# SEC_3002_HL_Loop1.net
KiCad netlist of a schematic drawn in Altium Designer
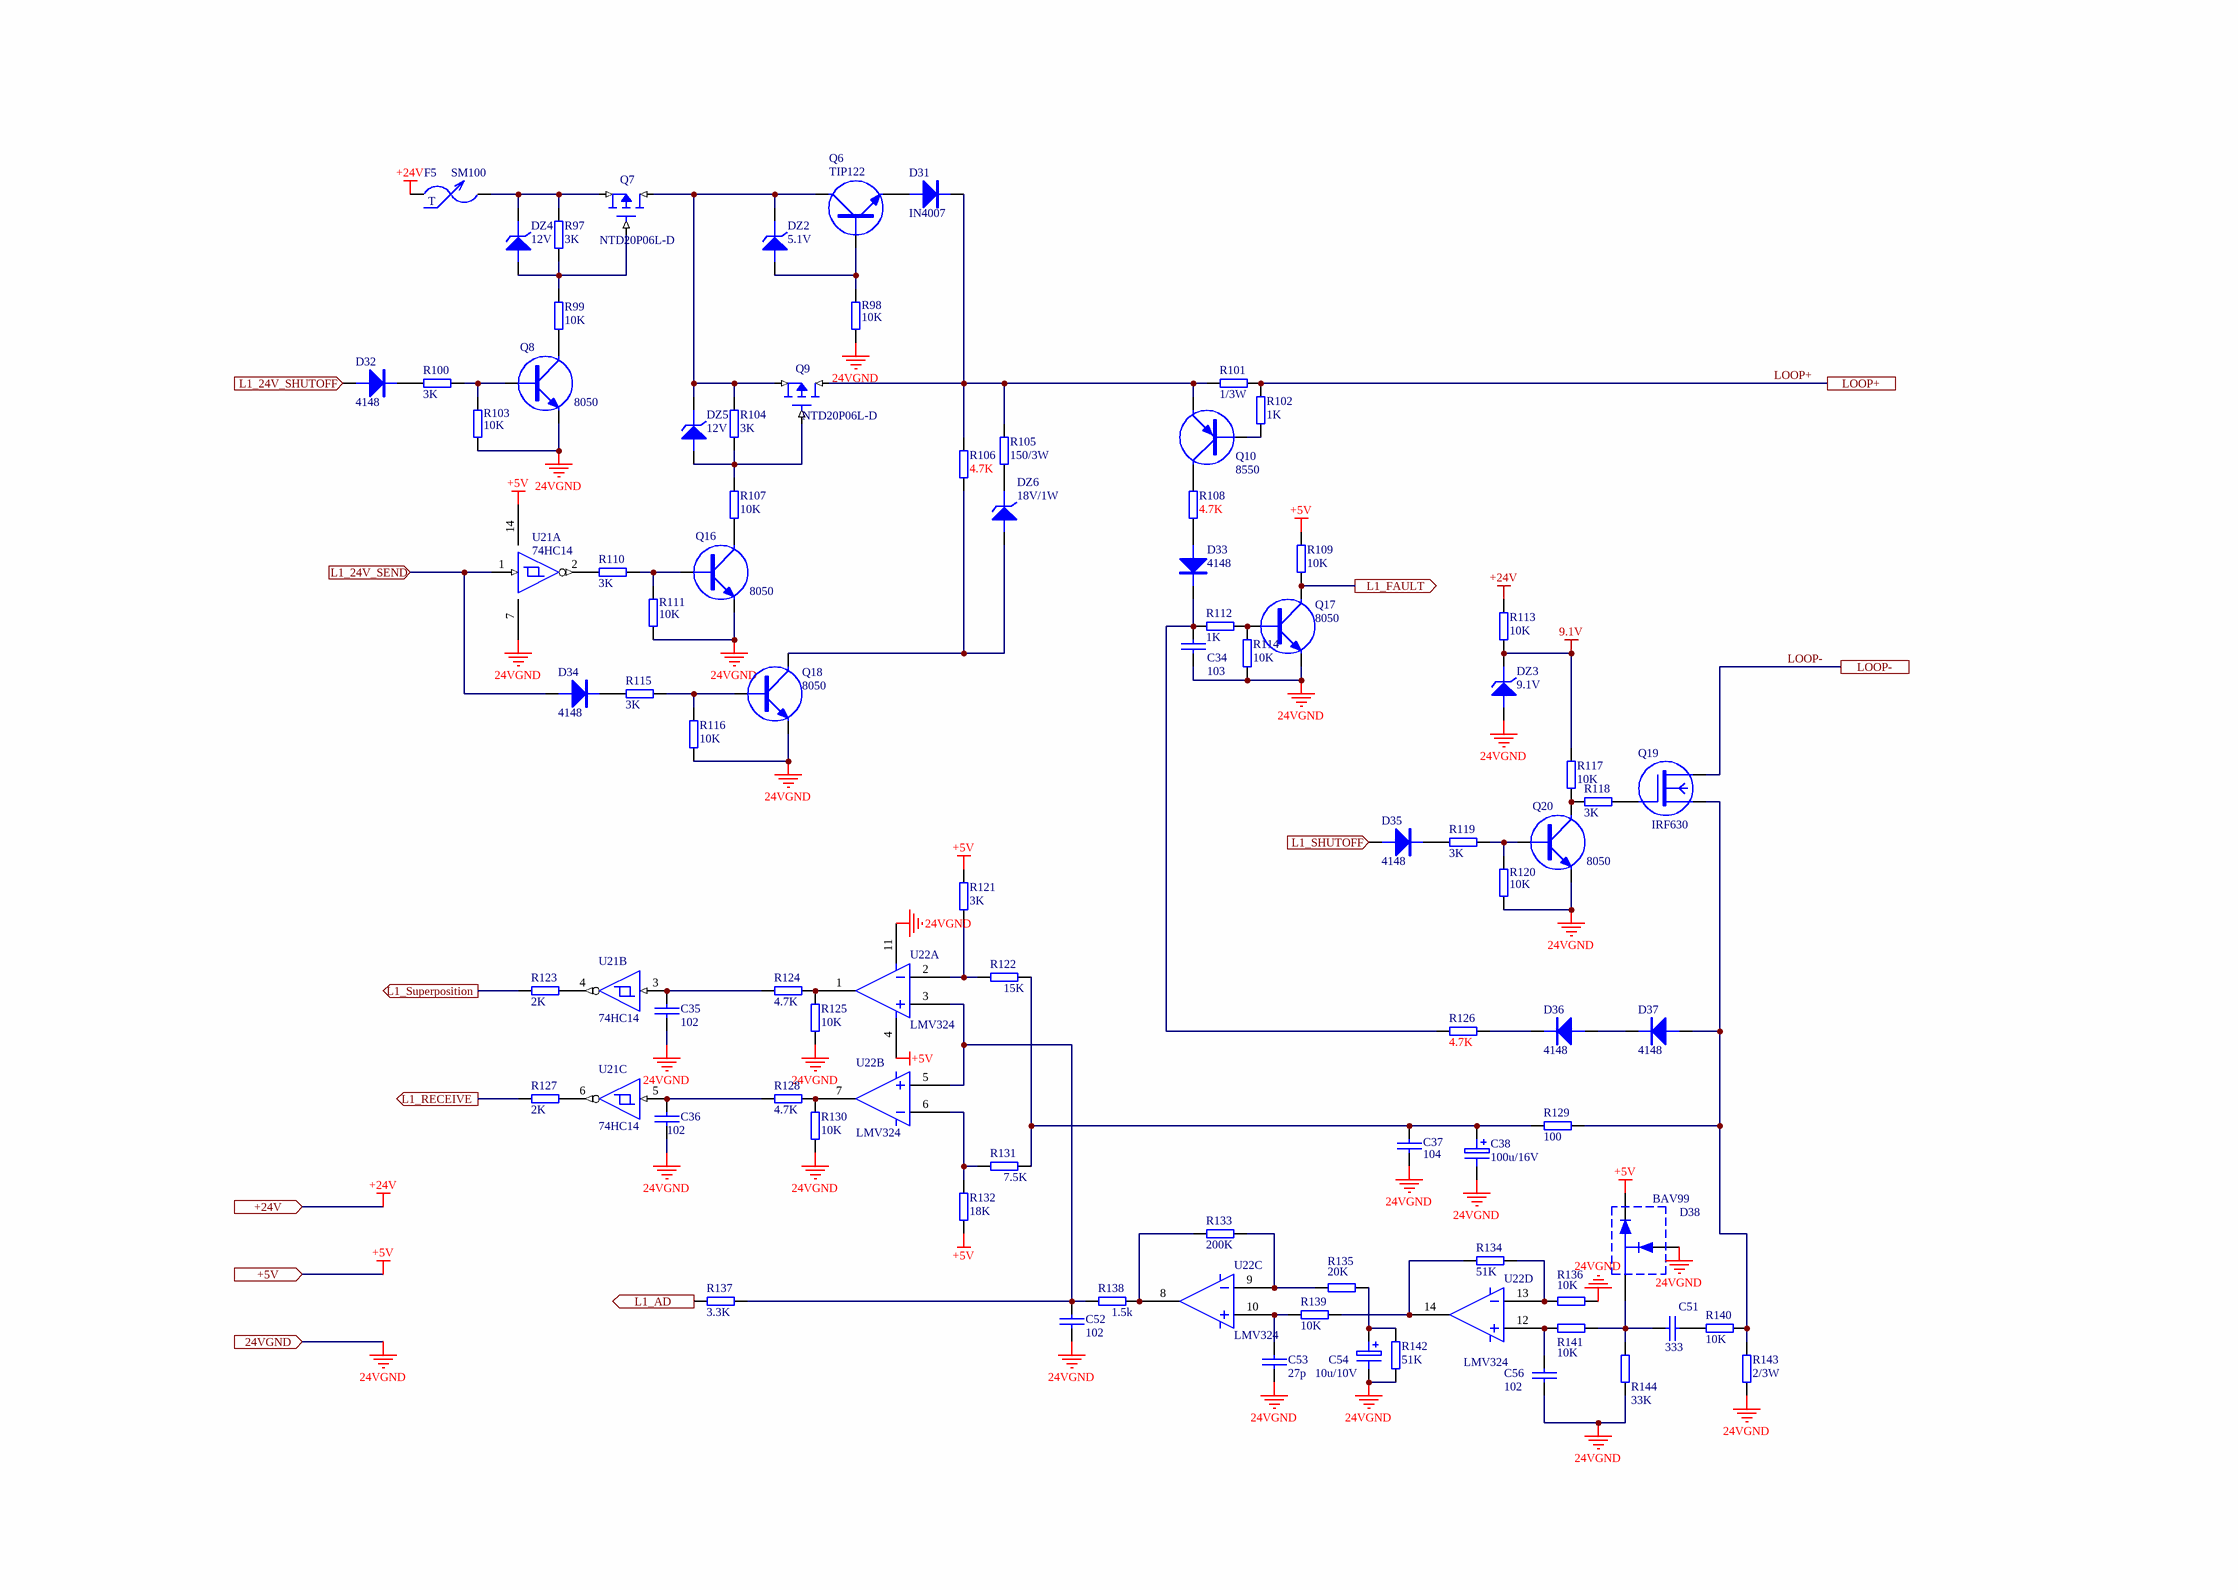
[diagram p0: SEC_3002_HL_Loop1.SchDoc]

(export (version "E")
  (design (tool "Eeschema 10.0.6"))
  (components
    (comp (ref "C34")
      (value "103")
      (footprint "C-0603")
      (description "Capacitor")
      (libsource (lib "*") (part "CAP"))
    )
    (comp (ref "C35")
      (value "102")
      (footprint "C-0603")
      (description "Capacitor")
      (libsource (lib "*") (part "CAP"))
    )
    (comp (ref "C36")
      (value "102")
      (footprint "C-0603")
      (description "Capacitor")
      (libsource (lib "*") (part "CAP"))
    )
    (comp (ref "C37")
      (value "104")
      (footprint "C-0603")
      (description "Capacitor")
      (libsource (lib "*") (part "CAP"))
    )
    (comp (ref "C38")
      (value "100u/16V")
      (footprint "CAP--SMD--6.6*5.3")
      (description "Electrolytic Capacitor")
      (libsource (lib "*") (part "ELECTRO1"))
    )
    (comp (ref "C51")
      (value "333")
      (footprint "C-0603")
      (description "Capacitor")
      (libsource (lib "*") (part "CAP"))
    )
    (comp (ref "C52")
      (value "102")
      (footprint "C-0603")
      (description "Capacitor")
      (libsource (lib "*") (part "CAP"))
    )
    (comp (ref "C53")
      (value "27p")
      (footprint "C-0603")
      (description "Capacitor")
      (libsource (lib "*") (part "CAP"))
    )
    (comp (ref "C54")
      (value "10u/10V")
      (footprint "C-0805")
      (description "Electrolytic Capacitor")
      (libsource (lib "*") (part "ELECTRO1"))
    )
    (comp (ref "C56")
      (value "102")
      (footprint "C-0603")
      (description "Capacitor")
      (libsource (lib "*") (part "CAP"))
    )
    (comp (ref "D31")
      (value "IN4007")
      (footprint "4526D")
      (description "Diode")
      (libsource (lib "*") (part "DIODE_A"))
    )
    (comp (ref "D32")
      (value "4148")
      (footprint "1206D")
      (description "Diode")
      (libsource (lib "*") (part "DIODE_A"))
    )
    (comp (ref "D33")
      (value "4148")
      (footprint "1206D")
      (description "Diode")
      (libsource (lib "*") (part "DIODE_A"))
    )
    (comp (ref "D34")
      (value "4148")
      (footprint "1206D")
      (description "Diode")
      (libsource (lib "*") (part "DIODE_A"))
    )
    (comp (ref "D35")
      (value "4148")
      (footprint "1206D")
      (description "Diode")
      (libsource (lib "*") (part "DIODE_A"))
    )
    (comp (ref "D36")
      (value "4148")
      (footprint "1206D")
      (description "Diode")
      (libsource (lib "*") (part "DIODE_A"))
    )
    (comp (ref "D37")
      (value "4148")
      (footprint "1206D")
      (description "Diode")
      (libsource (lib "*") (part "DIODE_A"))
    )
    (comp (ref "D38") (value "BAV99") (footprint "SOT-23") (libsource (lib "*") (part "BAV99")))
    (comp (ref "DZ2")
      (value "5.1V")
      (footprint "1206D")
      (description "Zener Diode")
      (libsource (lib "*") (part "ZENER3"))
    )
    (comp (ref "DZ3")
      (value "9.1V")
      (footprint "1206D")
      (description "Zener Diode")
      (libsource (lib "*") (part "ZENER3"))
    )
    (comp (ref "DZ4")
      (value "12V")
      (footprint "1206D")
      (description "Zener Diode")
      (libsource (lib "*") (part "ZENER3"))
    )
    (comp (ref "DZ5")
      (value "12V")
      (footprint "1206D")
      (description "Zener Diode")
      (libsource (lib "*") (part "ZENER3"))
    )
    (comp (ref "DZ6")
      (value "18V/1W")
      (footprint "1206D")
      (description "Zener Diode")
      (libsource (lib "*") (part "ZENER3"))
    )
    (comp (ref "F5")
      (value "SM100")
      (footprint "SM100")
      (description "PTC")
      (libsource (lib "*") (part "RXE110"))
    )
    (comp (ref "Q6")
      (value "TIP122")
      (footprint "TO252-(BCE)")
      (description "NPN Transistor")
      (libsource (lib "*") (part "NPN"))
    )
    (comp (ref "Q7")
      (value "NTD20P06L-D")
      (footprint "TO252-(GDS)")
      (description "P-channel mosfet")
      (libsource (lib "*") (part "MOSFET-P"))
    )
    (comp (ref "Q8")
      (value "8050")
      (footprint "SOT-23")
      (description "NPN Transistor")
      (libsource (lib "*") (part "NPN"))
    )
    (comp (ref "Q9")
      (value "NTD20P06L-D")
      (footprint "TO252-(GDS)")
      (description "P-channel mosfet")
      (libsource (lib "*") (part "MOSFET-P"))
    )
    (comp (ref "Q10")
      (value "8550")
      (footprint "SOT-23")
      (description "PNP Transistor")
      (libsource (lib "*") (part "PNP_A"))
    )
    (comp (ref "Q16")
      (value "8050")
      (footprint "SOT-23")
      (description "NPN Transistor")
      (libsource (lib "*") (part "NPN"))
    )
    (comp (ref "Q17")
      (value "8050")
      (footprint "SOT-23")
      (description "NPN Transistor")
      (libsource (lib "*") (part "NPN"))
    )
    (comp (ref "Q18")
      (value "8050")
      (footprint "SOT-23")
      (description "NPN Transistor")
      (libsource (lib "*") (part "NPN"))
    )
    (comp (ref "Q19") (value "IRF630") (footprint "TO252-(GDS)") (libsource (lib "*") (part "MOSFET-N1")))
    (comp (ref "Q20")
      (value "8050")
      (footprint "SOT-23")
      (description "NPN Transistor")
      (libsource (lib "*") (part "NPN"))
    )
    (comp (ref "R97") (value "3K") (footprint "R-0603") (libsource (lib "*") (part "RES2")))
    (comp (ref "R98") (value "10K") (footprint "R-0603") (libsource (lib "*") (part "RES2")))
    (comp (ref "R99") (value "10K") (footprint "R-0603") (libsource (lib "*") (part "RES2")))
    (comp (ref "R100") (value "3K") (footprint "R-0603") (libsource (lib "*") (part "RES2")))
    (comp (ref "R101") (value "1/3W") (footprint "AXIAL-0.8A") (libsource (lib "*") (part "RES2")))
    (comp (ref "R102") (value "1K") (footprint "R-0603") (libsource (lib "*") (part "RES2")))
    (comp (ref "R103") (value "10K") (footprint "R-0603") (libsource (lib "*") (part "RES2")))
    (comp (ref "R104") (value "3K") (footprint "R-0603") (libsource (lib "*") (part "RES2")))
    (comp (ref "R105") (value "150/3W") (footprint "AXIAL-0.8A") (libsource (lib "*") (part "RES2")))
    (comp (ref "R106") (value "4.7K") (footprint "R-0603") (libsource (lib "*") (part "RES2")))
    (comp (ref "R107") (value "10K") (footprint "R-0603") (libsource (lib "*") (part "RES2")))
    (comp (ref "R108") (value "4.7K") (footprint "R-0603") (libsource (lib "*") (part "RES2")))
    (comp (ref "R109") (value "10K") (footprint "R-0603") (libsource (lib "*") (part "RES2")))
    (comp (ref "R110") (value "3K") (footprint "R-0603") (libsource (lib "*") (part "RES2")))
    (comp (ref "R111") (value "10K") (footprint "R-0603") (libsource (lib "*") (part "RES2")))
    (comp (ref "R112") (value "1K") (footprint "R-0603") (libsource (lib "*") (part "RES2")))
    (comp (ref "R113") (value "10K") (footprint "R-0603") (libsource (lib "*") (part "RES2")))
    (comp (ref "R114") (value "10K") (footprint "R-0603") (libsource (lib "*") (part "RES2")))
    (comp (ref "R115") (value "3K") (footprint "R-0603") (libsource (lib "*") (part "RES2")))
    (comp (ref "R116") (value "10K") (footprint "R-0603") (libsource (lib "*") (part "RES2")))
    (comp (ref "R117") (value "10K") (footprint "R-0603") (libsource (lib "*") (part "RES2")))
    (comp (ref "R118") (value "3K") (footprint "R-0603") (libsource (lib "*") (part "RES2")))
    (comp (ref "R119") (value "3K") (footprint "R-0603") (libsource (lib "*") (part "RES2")))
    (comp (ref "R120") (value "10K") (footprint "R-0603") (libsource (lib "*") (part "RES2")))
    (comp (ref "R121") (value "3K") (footprint "R-0603") (libsource (lib "*") (part "RES2")))
    (comp (ref "R122") (value "15K") (footprint "R-0603") (libsource (lib "*") (part "RES2")))
    (comp (ref "R123") (value "2K") (footprint "R-0603") (libsource (lib "*") (part "RES2")))
    (comp (ref "R124") (value "4.7K") (footprint "R-0603") (libsource (lib "*") (part "RES2")))
    (comp (ref "R125") (value "10K") (footprint "R-0603") (libsource (lib "*") (part "RES2")))
    (comp (ref "R126") (value "4.7K") (footprint "R-0603") (libsource (lib "*") (part "RES2")))
    (comp (ref "R127") (value "2K") (footprint "R-0603") (libsource (lib "*") (part "RES2")))
    (comp (ref "R128") (value "4.7K") (footprint "R-0603") (libsource (lib "*") (part "RES2")))
    (comp (ref "R129") (value "100") (footprint "R-0603") (libsource (lib "*") (part "RES2")))
    (comp (ref "R130") (value "10K") (footprint "R-0603") (libsource (lib "*") (part "RES2")))
    (comp (ref "R131") (value "7.5K") (footprint "R-0603") (libsource (lib "*") (part "RES2")))
    (comp (ref "R132") (value "18K") (footprint "R-0603") (libsource (lib "*") (part "RES2")))
    (comp (ref "R133") (value "200K") (footprint "R-0603") (libsource (lib "*") (part "RES2")))
    (comp (ref "R134") (value "51K") (footprint "R-0603") (libsource (lib "*") (part "RES2")))
    (comp (ref "R135") (value "20K") (footprint "R-0603") (libsource (lib "*") (part "RES2")))
    (comp (ref "R136") (value "10K") (footprint "R-0603") (libsource (lib "*") (part "RES2")))
    (comp (ref "R137") (value "3.3K") (footprint "R-0603") (libsource (lib "*") (part "RES2")))
    (comp (ref "R138") (value "1.5k") (footprint "R-0603") (libsource (lib "*") (part "RES2")))
    (comp (ref "R139") (value "10K") (footprint "R-0603") (libsource (lib "*") (part "RES2")))
    (comp (ref "R140") (value "10K") (footprint "R-0603") (libsource (lib "*") (part "RES2")))
    (comp (ref "R141") (value "10K") (footprint "R-0603") (libsource (lib "*") (part "RES2")))
    (comp (ref "R142") (value "51K") (footprint "R-0603") (libsource (lib "*") (part "RES2")))
    (comp (ref "R143") (value "2/3W") (footprint "AXIAL-0.8A") (libsource (lib "*") (part "RES2")))
    (comp (ref "R144") (value "33K") (footprint "R-0603") (libsource (lib "*") (part "RES2")))
    (comp (ref "U21") (value "74HC14") (footprint "SO-14") (libsource (lib "LPCB_HL") (part "74LS14")))
    (comp (ref "U22") (value "LMV324") (footprint "SO-14") (libsource (lib "*") (part "LM124")))
  )
  (nets
    (net (code "1") (name "+5V") (class "Default")
      (node (ref "D38") (pin "E") (pinfunction "E_E") (pintype "passive"))
      (node (ref "R109") (pin "2") (pinfunction "2_2") (pintype "passive"))
      (node (ref "R121") (pin "1") (pinfunction "1_1") (pintype "passive"))
      (node (ref "R132") (pin "2") (pinfunction "2_2") (pintype "passive"))
      (node (ref "U21") (pin "14") (pinfunction "VCC_14") (pintype "passive"))
      (node (ref "U22") (pin "4") (pintype "passive"))
    )
    (net (code "2") (name "+24V") (class "Default")
      (node (ref "F5") (pin "2") (pinfunction "2_2") (pintype "passive"))
      (node (ref "R113") (pin "2") (pinfunction "2_2") (pintype "passive"))
    )
    (net (code "3") (name "/L1_24V_SEND") (class "Default")
      (node (ref "D34") (pin "A") (pinfunction "A_A") (pintype "passive"))
      (node (ref "U21") (pin "1") (pintype "input"))
    )
    (net (code "4") (name "/L1_24V_SHUTOFF") (class "Default")
      (node (ref "D32") (pin "A") (pinfunction "A_A") (pintype "passive"))
    )
    (net (code "5") (name "/L1_AD") (class "Default")
      (node (ref "R137") (pin "1") (pinfunction "1_1") (pintype "passive"))
    )
    (net (code "6") (name "/L1_FAULT") (class "Default")
      (node (ref "Q17") (pin "C") (pinfunction "C_C") (pintype "passive"))
      (node (ref "R109") (pin "1") (pinfunction "1_1") (pintype "passive"))
    )
    (net (code "7") (name "/L1_RECEIVE") (class "Default")
      (node (ref "R127") (pin "2") (pinfunction "2_2") (pintype "passive"))
    )
    (net (code "8") (name "/L1_SHUTOFF") (class "Default")
      (node (ref "D35") (pin "A") (pinfunction "A_A") (pintype "passive"))
    )
    (net (code "9") (name "/L1_Superposition") (class "Default")
      (node (ref "R123") (pin "2") (pinfunction "2_2") (pintype "passive"))
    )
    (net (code "10") (name "/LOOP+") (class "Default")
      (node (ref "R101") (pin "2") (pinfunction "2_2") (pintype "passive"))
      (node (ref "R102") (pin "2") (pinfunction "2_2") (pintype "passive"))
    )
    (net (code "11") (name "/LOOP-") (class "Default")
      (node (ref "Q19") (pin "D") (pinfunction "D_D") (pintype "passive"))
    )
    (net (code "12") (name "9.1V") (class "Default")
      (node (ref "DZ3") (pin "K") (pinfunction "K_K") (pintype "passive"))
      (node (ref "R113") (pin "1") (pinfunction "1_1") (pintype "passive"))
      (node (ref "R117") (pin "2") (pinfunction "2_2") (pintype "passive"))
    )
    (net (code "13") (name "24VGND") (class "Default")
      (node (ref "C34") (pin "2") (pinfunction "2_2") (pintype "passive"))
      (node (ref "C35") (pin "2") (pinfunction "2_2") (pintype "passive"))
      (node (ref "C36") (pin "2") (pinfunction "2_2") (pintype "passive"))
      (node (ref "C37") (pin "1") (pinfunction "1_1") (pintype "passive"))
      (node (ref "C38") (pin "2") (pinfunction "2_2") (pintype "passive"))
      (node (ref "C52") (pin "2") (pinfunction "2_2") (pintype "passive"))
      (node (ref "C53") (pin "1") (pinfunction "1_1") (pintype "passive"))
      (node (ref "C54") (pin "2") (pinfunction "2_2") (pintype "passive"))
      (node (ref "C56") (pin "2") (pinfunction "2_2") (pintype "passive"))
      (node (ref "D38") (pin "B") (pinfunction "B_B") (pintype "passive"))
      (node (ref "DZ3") (pin "A") (pinfunction "A_A") (pintype "passive"))
      (node (ref "Q16") (pin "E") (pinfunction "E_E") (pintype "passive"))
      (node (ref "Q17") (pin "E") (pinfunction "E_E") (pintype "passive"))
      (node (ref "Q18") (pin "E") (pinfunction "E_E") (pintype "passive"))
      (node (ref "Q20") (pin "E") (pinfunction "E_E") (pintype "passive"))
      (node (ref "Q8") (pin "E") (pinfunction "E_E") (pintype "passive"))
      (node (ref "R103") (pin "1") (pinfunction "1_1") (pintype "passive"))
      (node (ref "R111") (pin "1") (pinfunction "1_1") (pintype "passive"))
      (node (ref "R114") (pin "1") (pinfunction "1_1") (pintype "passive"))
      (node (ref "R116") (pin "1") (pinfunction "1_1") (pintype "passive"))
      (node (ref "R120") (pin "1") (pinfunction "1_1") (pintype "passive"))
      (node (ref "R125") (pin "1") (pinfunction "1_1") (pintype "passive"))
      (node (ref "R130") (pin "1") (pinfunction "1_1") (pintype "passive"))
      (node (ref "R136") (pin "1") (pinfunction "1_1") (pintype "passive"))
      (node (ref "R142") (pin "2") (pinfunction "2_2") (pintype "passive"))
      (node (ref "R143") (pin "2") (pinfunction "2_2") (pintype "passive"))
      (node (ref "R144") (pin "2") (pinfunction "2_2") (pintype "passive"))
      (node (ref "R98") (pin "1") (pinfunction "1_1") (pintype "passive"))
      (node (ref "U21") (pin "7") (pinfunction "GND_7") (pintype "passive"))
      (node (ref "U22") (pin "11") (pintype "passive"))
    )
    (net (code "14") (name "Net-(C34-Pad1)") (class "Default")
      (node (ref "C34") (pin "1") (pinfunction "1_1") (pintype "passive"))
      (node (ref "D33") (pin "K") (pinfunction "K_K") (pintype "passive"))
      (node (ref "R112") (pin "2") (pinfunction "2_2") (pintype "passive"))
      (node (ref "R126") (pin "2") (pinfunction "2_2") (pintype "passive"))
    )
    (net (code "15") (name "Net-(C35-Pad1)") (class "Default")
      (node (ref "C35") (pin "1") (pinfunction "1_1") (pintype "passive"))
      (node (ref "R124") (pin "2") (pinfunction "2_2") (pintype "passive"))
      (node (ref "U21") (pin "3") (pintype "input"))
    )
    (net (code "16") (name "Net-(C36-Pad1)") (class "Default")
      (node (ref "C36") (pin "1") (pinfunction "1_1") (pintype "passive"))
      (node (ref "R128") (pin "2") (pinfunction "2_2") (pintype "passive"))
      (node (ref "U21") (pin "5") (pintype "input"))
    )
    (net (code "17") (name "Net-(C37-Pad2)") (class "Default")
      (node (ref "C37") (pin "2") (pinfunction "2_2") (pintype "passive"))
      (node (ref "C38") (pin "1") (pinfunction "1_1") (pintype "passive"))
      (node (ref "R122") (pin "1") (pinfunction "1_1") (pintype "passive"))
      (node (ref "R129") (pin "2") (pinfunction "2_2") (pintype "passive"))
      (node (ref "R131") (pin "1") (pinfunction "1_1") (pintype "passive"))
    )
    (net (code "18") (name "Net-(C51-Pad1)") (class "Default")
      (node (ref "C51") (pin "1") (pinfunction "1_1") (pintype "passive"))
      (node (ref "R140") (pin "2") (pinfunction "2_2") (pintype "passive"))
    )
    (net (code "19") (name "Net-(C51-Pad2)") (class "Default")
      (node (ref "C51") (pin "2") (pinfunction "2_2") (pintype "passive"))
      (node (ref "D38") (pin "C") (pinfunction "C_C") (pintype "passive"))
      (node (ref "R141") (pin "1") (pinfunction "1_1") (pintype "passive"))
      (node (ref "R144") (pin "1") (pinfunction "1_1") (pintype "passive"))
    )
    (net (code "20") (name "Net-(C52-Pad1)") (class "Default")
      (node (ref "C52") (pin "1") (pinfunction "1_1") (pintype "passive"))
      (node (ref "R137") (pin "2") (pinfunction "2_2") (pintype "passive"))
      (node (ref "R138") (pin "2") (pinfunction "2_2") (pintype "passive"))
      (node (ref "U22") (pin "3") (pintype "passive"))
      (node (ref "U22") (pin "5") (pintype "passive"))
    )
    (net (code "21") (name "Net-(C53-Pad2)") (class "Default")
      (node (ref "C53") (pin "2") (pinfunction "2_2") (pintype "passive"))
      (node (ref "R139") (pin "2") (pinfunction "2_2") (pintype "passive"))
      (node (ref "U22") (pin "10") (pintype "passive"))
    )
    (net (code "22") (name "Net-(C54-Pad1)") (class "Default")
      (node (ref "C54") (pin "1") (pinfunction "1_1") (pintype "passive"))
      (node (ref "R135") (pin "1") (pinfunction "1_1") (pintype "passive"))
      (node (ref "R142") (pin "1") (pinfunction "1_1") (pintype "passive"))
    )
    (net (code "23") (name "Net-(C56-Pad1)") (class "Default")
      (node (ref "C56") (pin "1") (pinfunction "1_1") (pintype "passive"))
      (node (ref "R141") (pin "2") (pinfunction "2_2") (pintype "passive"))
      (node (ref "U22") (pin "12") (pintype "passive"))
    )
    (net (code "24") (name "Net-(D31-PadA)") (class "Default")
      (node (ref "D31") (pin "A") (pinfunction "A_A") (pintype "passive"))
      (node (ref "Q6") (pin "E") (pinfunction "E_E") (pintype "passive"))
    )
    (net (code "25") (name "Net-(D31-PadK)") (class "Default")
      (node (ref "D31") (pin "K") (pinfunction "K_K") (pintype "passive"))
      (node (ref "Q10") (pin "E") (pinfunction "E_E") (pintype "passive"))
      (node (ref "Q9") (pin "D") (pinfunction "D_D") (pintype "input"))
      (node (ref "R101") (pin "1") (pinfunction "1_1") (pintype "passive"))
      (node (ref "R105") (pin "1") (pinfunction "1_1") (pintype "passive"))
      (node (ref "R106") (pin "1") (pinfunction "1_1") (pintype "passive"))
    )
    (net (code "26") (name "Net-(D32-PadK)") (class "Default")
      (node (ref "D32") (pin "K") (pinfunction "K_K") (pintype "passive"))
      (node (ref "R100") (pin "2") (pinfunction "2_2") (pintype "passive"))
    )
    (net (code "27") (name "Net-(D33-PadA)") (class "Default")
      (node (ref "D33") (pin "A") (pinfunction "A_A") (pintype "passive"))
      (node (ref "R108") (pin "1") (pinfunction "1_1") (pintype "passive"))
    )
    (net (code "28") (name "Net-(D34-PadK)") (class "Default")
      (node (ref "D34") (pin "K") (pinfunction "K_K") (pintype "passive"))
      (node (ref "R115") (pin "1") (pinfunction "1_1") (pintype "passive"))
    )
    (net (code "29") (name "Net-(D35-PadK)") (class "Default")
      (node (ref "D35") (pin "K") (pinfunction "K_K") (pintype "passive"))
      (node (ref "R119") (pin "1") (pinfunction "1_1") (pintype "passive"))
    )
    (net (code "30") (name "Net-(D36-PadA)") (class "Default")
      (node (ref "D36") (pin "A") (pinfunction "A_A") (pintype "passive"))
      (node (ref "D37") (pin "K") (pinfunction "K_K") (pintype "passive"))
    )
    (net (code "31") (name "Net-(D36-PadK)") (class "Default")
      (node (ref "D36") (pin "K") (pinfunction "K_K") (pintype "passive"))
      (node (ref "R126") (pin "1") (pinfunction "1_1") (pintype "passive"))
    )
    (net (code "32") (name "Net-(D37-PadA)") (class "Default")
      (node (ref "D37") (pin "A") (pinfunction "A_A") (pintype "passive"))
      (node (ref "Q19") (pin "S") (pinfunction "S_S") (pintype "passive"))
      (node (ref "R129") (pin "1") (pinfunction "1_1") (pintype "passive"))
      (node (ref "R140") (pin "1") (pinfunction "1_1") (pintype "passive"))
      (node (ref "R143") (pin "1") (pinfunction "1_1") (pintype "passive"))
    )
    (net (code "33") (name "Net-(DZ2-PadA)") (class "Default")
      (node (ref "DZ2") (pin "A") (pinfunction "A_A") (pintype "passive"))
      (node (ref "Q6") (pin "B") (pinfunction "B_B") (pintype "passive"))
      (node (ref "R98") (pin "2") (pinfunction "2_2") (pintype "passive"))
    )
    (net (code "34") (name "Net-(DZ2-PadK)") (class "Default")
      (node (ref "DZ2") (pin "K") (pinfunction "K_K") (pintype "passive"))
      (node (ref "DZ5") (pin "K") (pinfunction "K_K") (pintype "passive"))
      (node (ref "Q6") (pin "C") (pinfunction "C_C") (pintype "passive"))
      (node (ref "Q7") (pin "D") (pinfunction "D_D") (pintype "input"))
      (node (ref "Q9") (pin "S") (pinfunction "S_S") (pintype "input"))
      (node (ref "R104") (pin "2") (pinfunction "2_2") (pintype "passive"))
    )
    (net (code "35") (name "Net-(DZ4-PadA)") (class "Default")
      (node (ref "DZ4") (pin "A") (pinfunction "A_A") (pintype "passive"))
      (node (ref "Q7") (pin "G") (pinfunction "G_G") (pintype "input"))
      (node (ref "R97") (pin "1") (pinfunction "1_1") (pintype "passive"))
      (node (ref "R99") (pin "2") (pinfunction "2_2") (pintype "passive"))
    )
    (net (code "36") (name "Net-(DZ4-PadK)") (class "Default")
      (node (ref "DZ4") (pin "K") (pinfunction "K_K") (pintype "passive"))
      (node (ref "F5") (pin "1") (pinfunction "1_1") (pintype "passive"))
      (node (ref "Q7") (pin "S") (pinfunction "S_S") (pintype "input"))
      (node (ref "R97") (pin "2") (pinfunction "2_2") (pintype "passive"))
    )
    (net (code "37") (name "Net-(DZ5-PadA)") (class "Default")
      (node (ref "DZ5") (pin "A") (pinfunction "A_A") (pintype "passive"))
      (node (ref "Q9") (pin "G") (pinfunction "G_G") (pintype "input"))
      (node (ref "R104") (pin "1") (pinfunction "1_1") (pintype "passive"))
      (node (ref "R107") (pin "2") (pinfunction "2_2") (pintype "passive"))
    )
    (net (code "38") (name "Net-(DZ6-PadA)") (class "Default")
      (node (ref "DZ6") (pin "A") (pinfunction "A_A") (pintype "passive"))
      (node (ref "Q18") (pin "C") (pinfunction "C_C") (pintype "passive"))
      (node (ref "R106") (pin "2") (pinfunction "2_2") (pintype "passive"))
    )
    (net (code "39") (name "Net-(DZ6-PadK)") (class "Default")
      (node (ref "DZ6") (pin "K") (pinfunction "K_K") (pintype "passive"))
      (node (ref "R105") (pin "2") (pinfunction "2_2") (pintype "passive"))
    )
    (net (code "40") (name "Net-(Q8-PadB)") (class "Default")
      (node (ref "Q8") (pin "B") (pinfunction "B_B") (pintype "passive"))
      (node (ref "R100") (pin "1") (pinfunction "1_1") (pintype "passive"))
      (node (ref "R103") (pin "2") (pinfunction "2_2") (pintype "passive"))
    )
    (net (code "41") (name "Net-(Q8-PadC)") (class "Default")
      (node (ref "Q8") (pin "C") (pinfunction "C_C") (pintype "passive"))
      (node (ref "R99") (pin "1") (pinfunction "1_1") (pintype "passive"))
    )
    (net (code "42") (name "Net-(Q10-PadB)") (class "Default")
      (node (ref "Q10") (pin "B") (pinfunction "B_B") (pintype "passive"))
      (node (ref "R102") (pin "1") (pinfunction "1_1") (pintype "passive"))
    )
    (net (code "43") (name "Net-(Q10-PadC)") (class "Default")
      (node (ref "Q10") (pin "C") (pinfunction "C_C") (pintype "passive"))
      (node (ref "R108") (pin "2") (pinfunction "2_2") (pintype "passive"))
    )
    (net (code "44") (name "Net-(Q16-PadB)") (class "Default")
      (node (ref "Q16") (pin "B") (pinfunction "B_B") (pintype "passive"))
      (node (ref "R110") (pin "1") (pinfunction "1_1") (pintype "passive"))
      (node (ref "R111") (pin "2") (pinfunction "2_2") (pintype "passive"))
    )
    (net (code "45") (name "Net-(Q16-PadC)") (class "Default")
      (node (ref "Q16") (pin "C") (pinfunction "C_C") (pintype "passive"))
      (node (ref "R107") (pin "1") (pinfunction "1_1") (pintype "passive"))
    )
    (net (code "46") (name "Net-(Q17-PadB)") (class "Default")
      (node (ref "Q17") (pin "B") (pinfunction "B_B") (pintype "passive"))
      (node (ref "R112") (pin "1") (pinfunction "1_1") (pintype "passive"))
      (node (ref "R114") (pin "2") (pinfunction "2_2") (pintype "passive"))
    )
    (net (code "47") (name "Net-(Q18-PadB)") (class "Default")
      (node (ref "Q18") (pin "B") (pinfunction "B_B") (pintype "passive"))
      (node (ref "R115") (pin "2") (pinfunction "2_2") (pintype "passive"))
      (node (ref "R116") (pin "2") (pinfunction "2_2") (pintype "passive"))
    )
    (net (code "48") (name "Net-(Q19-PadG)") (class "Default")
      (node (ref "Q19") (pin "G") (pinfunction "G_G") (pintype "passive"))
      (node (ref "R118") (pin "1") (pinfunction "1_1") (pintype "passive"))
    )
    (net (code "49") (name "Net-(Q20-PadB)") (class "Default")
      (node (ref "Q20") (pin "B") (pinfunction "B_B") (pintype "passive"))
      (node (ref "R119") (pin "2") (pinfunction "2_2") (pintype "passive"))
      (node (ref "R120") (pin "2") (pinfunction "2_2") (pintype "passive"))
    )
    (net (code "50") (name "Net-(Q20-PadC)") (class "Default")
      (node (ref "Q20") (pin "C") (pinfunction "C_C") (pintype "passive"))
      (node (ref "R117") (pin "1") (pinfunction "1_1") (pintype "passive"))
      (node (ref "R118") (pin "2") (pinfunction "2_2") (pintype "passive"))
    )
    (net (code "51") (name "Net-(R110-Pad2)") (class "Default")
      (node (ref "R110") (pin "2") (pinfunction "2_2") (pintype "passive"))
      (node (ref "U21") (pin "2") (pintype "output"))
    )
    (net (code "52") (name "Net-(R121-Pad2)") (class "Default")
      (node (ref "R121") (pin "2") (pinfunction "2_2") (pintype "passive"))
      (node (ref "R122") (pin "2") (pinfunction "2_2") (pintype "passive"))
      (node (ref "U22") (pin "2") (pintype "passive"))
    )
    (net (code "53") (name "Net-(R123-Pad1)") (class "Default")
      (node (ref "R123") (pin "1") (pinfunction "1_1") (pintype "passive"))
      (node (ref "U21") (pin "4") (pintype "output"))
    )
    (net (code "54") (name "Net-(R124-Pad1)") (class "Default")
      (node (ref "R124") (pin "1") (pinfunction "1_1") (pintype "passive"))
      (node (ref "R125") (pin "2") (pinfunction "2_2") (pintype "passive"))
      (node (ref "U22") (pin "1") (pintype "passive"))
    )
    (net (code "55") (name "Net-(R127-Pad1)") (class "Default")
      (node (ref "R127") (pin "1") (pinfunction "1_1") (pintype "passive"))
      (node (ref "U21") (pin "6") (pintype "output"))
    )
    (net (code "56") (name "Net-(R128-Pad1)") (class "Default")
      (node (ref "R128") (pin "1") (pinfunction "1_1") (pintype "passive"))
      (node (ref "R130") (pin "2") (pinfunction "2_2") (pintype "passive"))
      (node (ref "U22") (pin "7") (pintype "passive"))
    )
    (net (code "57") (name "Net-(R131-Pad2)") (class "Default")
      (node (ref "R131") (pin "2") (pinfunction "2_2") (pintype "passive"))
      (node (ref "R132") (pin "1") (pinfunction "1_1") (pintype "passive"))
      (node (ref "U22") (pin "6") (pintype "passive"))
    )
    (net (code "58") (name "Net-(R133-Pad1)") (class "Default")
      (node (ref "R133") (pin "1") (pinfunction "1_1") (pintype "passive"))
      (node (ref "R135") (pin "2") (pinfunction "2_2") (pintype "passive"))
      (node (ref "U22") (pin "9") (pintype "passive"))
    )
    (net (code "59") (name "Net-(R133-Pad2)") (class "Default")
      (node (ref "R133") (pin "2") (pinfunction "2_2") (pintype "passive"))
      (node (ref "R138") (pin "1") (pinfunction "1_1") (pintype "passive"))
      (node (ref "U22") (pin "8") (pintype "passive"))
    )
    (net (code "60") (name "Net-(R134-Pad1)") (class "Default")
      (node (ref "R134") (pin "1") (pinfunction "1_1") (pintype "passive"))
      (node (ref "R136") (pin "2") (pinfunction "2_2") (pintype "passive"))
      (node (ref "U22") (pin "13") (pintype "passive"))
    )
    (net (code "61") (name "Net-(R134-Pad2)") (class "Default")
      (node (ref "R134") (pin "2") (pinfunction "2_2") (pintype "passive"))
      (node (ref "R139") (pin "1") (pinfunction "1_1") (pintype "passive"))
      (node (ref "U22") (pin "14") (pintype "passive"))
    )
  )
)
